# femto.net
KiCad netlist of a schematic drawn in EAGLE
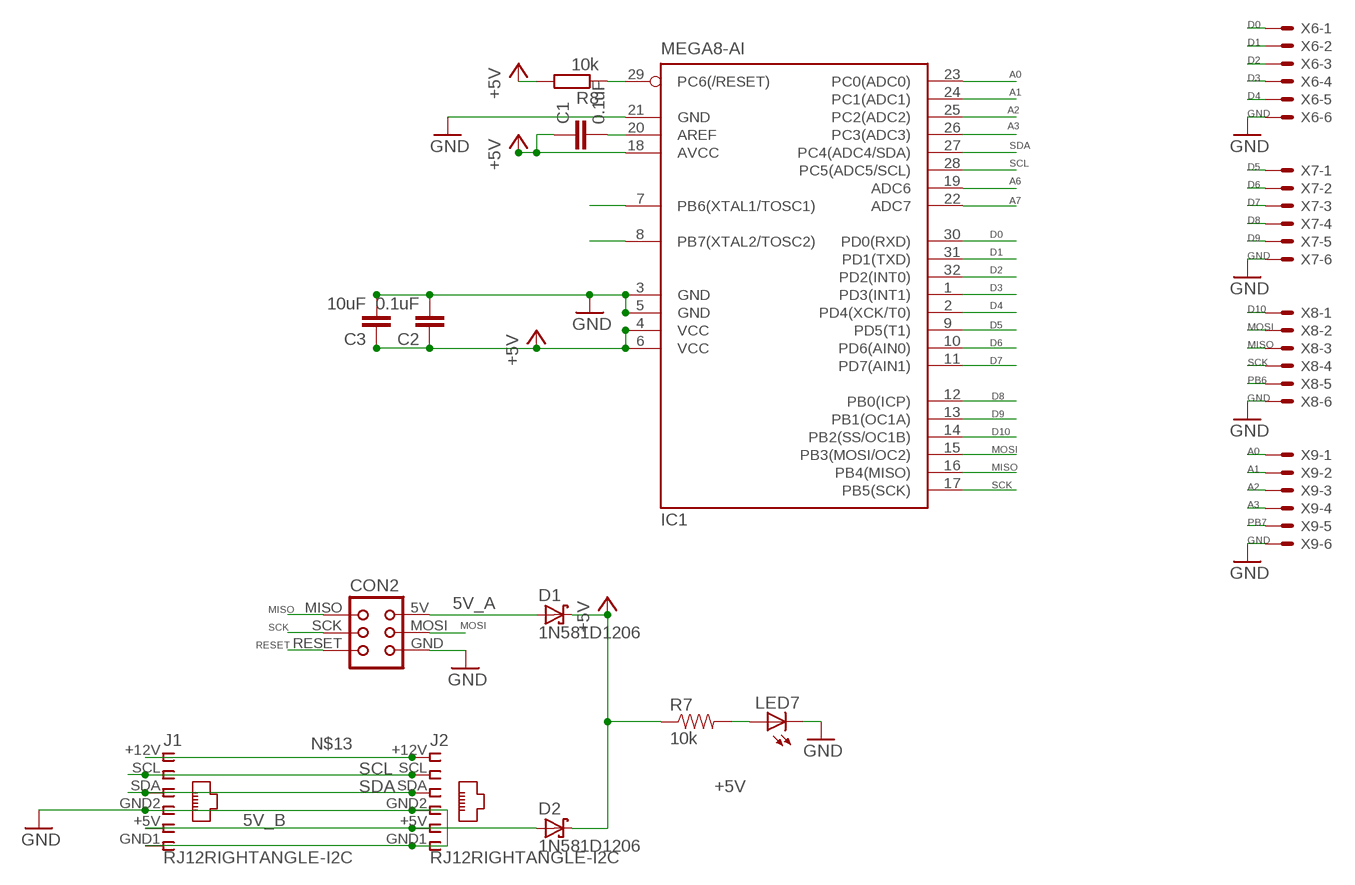
[diagram p0: schematic, sheet 1]

(export (version "E")
  (design (tool "Eeschema 10.0.6"))
  (components
    (comp (ref "C1")
      (value "0.1uF")
      (footprint "eagle-import:C1206")
      (libsource (lib "eagle-import") (part "C-EUC1206"))
    )
    (comp (ref "C2")
      (value "0.1uF")
      (footprint "eagle-import:C1206")
      (libsource (lib "eagle-import") (part "C-EUC1206"))
    )
    (comp (ref "C3")
      (value "10uF")
      (footprint "eagle-import:C1206")
      (libsource (lib "eagle-import") (part "C-EUC1206"))
    )
    (comp (ref "CON2")
      (value "TINYISPTAG")
      (footprint "eagle-import:TC2030-MCP")
      (libsource (lib "eagle-import") (part "TINYISPTAG"))
    )
    (comp (ref "D1")
      (value "1N581D1206")
      (footprint "eagle-import:LED-1206")
      (libsource (lib "eagle-import") (part "1N581D1206"))
    )
    (comp (ref "D2")
      (value "1N581D1206")
      (footprint "eagle-import:LED-1206")
      (libsource (lib "eagle-import") (part "1N581D1206"))
    )
    (comp (ref "IC1")
      (value "MEGA8-AI")
      (footprint "eagle-import:TQFP32-08")
      (fields (field (name "MPN") "ATMEGA8-16AU"))
      (libsource (lib "eagle-import") (part "MEGA8-AI"))
    )
    (comp (ref "J1")
      (value "RJ12RIGHTANGLE-I2C")
      (footprint "eagle-import:RJ12-RIGHTANGLE-I2C")
      (libsource (lib "eagle-import") (part "RJ12RIGHTANGLE-I2C"))
    )
    (comp (ref "J2")
      (value "RJ12RIGHTANGLE-I2C")
      (footprint "eagle-import:RJ12-RIGHTANGLE-I2C")
      (libsource (lib "eagle-import") (part "RJ12RIGHTANGLE-I2C"))
    )
    (comp (ref "LED7")
      (value "LEDCHIP-LED0603")
      (footprint "eagle-import:CHIP-LED0603")
      (libsource (lib "eagle-import") (part "LEDCHIP-LED0603"))
    )
    (comp (ref "R7")
      (value "10k")
      (footprint "eagle-import:0603-RES")
      (libsource (lib "eagle-import") (part "RESISTOR0603-RES"))
    )
    (comp (ref "R8")
      (value "10k")
      (footprint "eagle-import:M1206")
      (libsource (lib "eagle-import") (part "R-EU_M1206"))
    )
    (comp (ref "X6")
      (value "22-23-2061")
      (footprint "eagle-import:22-23-2061")
      (fields (field (name "MF") "MOLEX"))
      (libsource (lib "eagle-import") (part "22-23-2061"))
    )
    (comp (ref "X7")
      (value "22-23-2061")
      (footprint "eagle-import:22-23-2061")
      (fields (field (name "MF") "MOLEX"))
      (libsource (lib "eagle-import") (part "22-23-2061"))
    )
    (comp (ref "X8")
      (value "22-23-2061")
      (footprint "eagle-import:22-23-2061")
      (fields (field (name "MF") "MOLEX"))
      (libsource (lib "eagle-import") (part "22-23-2061"))
    )
    (comp (ref "X9")
      (value "22-23-2061")
      (footprint "eagle-import:22-23-2061")
      (fields (field (name "MF") "MOLEX"))
      (libsource (lib "eagle-import") (part "22-23-2061"))
    )
  )
  (nets
    (net (code "1") (name "+5V") (class "Default")
      (node (ref "C1") (pin "1") (pinfunction "1_1") (pintype "passive"))
      (node (ref "C2") (pin "1") (pinfunction "1_1") (pintype "passive"))
      (node (ref "C3") (pin "1") (pinfunction "1_1") (pintype "passive"))
      (node (ref "D1") (pin "C") (pinfunction "C_C") (pintype "passive"))
      (node (ref "D2") (pin "C") (pinfunction "C_C") (pintype "passive"))
      (node (ref "IC1") (pin "18") (pinfunction "AVCC_18") (pintype "power_in"))
      (node (ref "IC1") (pin "4") (pinfunction "VCC_4") (pintype "power_in"))
      (node (ref "IC1") (pin "6") (pinfunction "VCC_6") (pintype "power_in"))
      (node (ref "R7") (pin "1") (pinfunction "1_1") (pintype "passive"))
      (node (ref "R8") (pin "2") (pinfunction "2_2") (pintype "passive"))
    )
    (net (code "2") (name "/5V_A") (class "Default")
      (node (ref "CON2") (pin "5V") (pinfunction "VCC_5V") (pintype "passive"))
      (node (ref "D1") (pin "A") (pinfunction "A_A") (pintype "passive"))
    )
    (net (code "3") (name "/5V_B") (class "Default")
      (node (ref "D2") (pin "A") (pinfunction "A_A") (pintype "passive"))
      (node (ref "J1") (pin "+5V") (pinfunction "5_+5V") (pintype "bidirectional"))
      (node (ref "J2") (pin "+5V") (pinfunction "5_+5V") (pintype "bidirectional"))
    )
    (net (code "4") (name "/A0") (class "Default")
      (node (ref "IC1") (pin "23") (pinfunction "PC0(ADC0)_23") (pintype "bidirectional"))
      (node (ref "X9") (pin "1") (pinfunction "S_1") (pintype "passive"))
    )
    (net (code "5") (name "/A1") (class "Default")
      (node (ref "IC1") (pin "24") (pinfunction "PC1(ADC1)_24") (pintype "bidirectional"))
      (node (ref "X9") (pin "2") (pinfunction "S_2") (pintype "passive"))
    )
    (net (code "6") (name "/A2") (class "Default")
      (node (ref "IC1") (pin "25") (pinfunction "PC2(ADC2)_25") (pintype "bidirectional"))
      (node (ref "X9") (pin "3") (pinfunction "S_3") (pintype "passive"))
    )
    (net (code "7") (name "/A3") (class "Default")
      (node (ref "IC1") (pin "26") (pinfunction "PC3(ADC3)_26") (pintype "bidirectional"))
      (node (ref "X9") (pin "4") (pinfunction "S_4") (pintype "passive"))
    )
    (net (code "8") (name "/A6") (class "Default")
      (node (ref "IC1") (pin "19") (pinfunction "ADC6_19") (pintype "bidirectional"))
    )
    (net (code "9") (name "/A7") (class "Default")
      (node (ref "IC1") (pin "22") (pinfunction "ADC7_22") (pintype "bidirectional"))
    )
    (net (code "10") (name "/D0") (class "Default")
      (node (ref "IC1") (pin "30") (pinfunction "PD0(RXD)_30") (pintype "bidirectional"))
      (node (ref "X6") (pin "1") (pinfunction "S_1") (pintype "passive"))
    )
    (net (code "11") (name "/D1") (class "Default")
      (node (ref "IC1") (pin "31") (pinfunction "PD1(TXD)_31") (pintype "bidirectional"))
      (node (ref "X6") (pin "2") (pinfunction "S_2") (pintype "passive"))
    )
    (net (code "12") (name "/D2") (class "Default")
      (node (ref "IC1") (pin "32") (pinfunction "PD2(INT0)_32") (pintype "bidirectional"))
      (node (ref "X6") (pin "3") (pinfunction "S_3") (pintype "passive"))
    )
    (net (code "13") (name "/D3") (class "Default")
      (node (ref "IC1") (pin "1") (pinfunction "PD3(INT1)_1") (pintype "bidirectional"))
      (node (ref "X6") (pin "4") (pinfunction "S_4") (pintype "passive"))
    )
    (net (code "14") (name "/D4") (class "Default")
      (node (ref "IC1") (pin "2") (pinfunction "PD4(XCK/T0)_2") (pintype "bidirectional"))
      (node (ref "X6") (pin "5") (pinfunction "S_5") (pintype "passive"))
    )
    (net (code "15") (name "/D5") (class "Default")
      (node (ref "IC1") (pin "9") (pinfunction "PD5(T1)_9") (pintype "bidirectional"))
      (node (ref "X7") (pin "1") (pinfunction "S_1") (pintype "passive"))
    )
    (net (code "16") (name "/D6") (class "Default")
      (node (ref "IC1") (pin "10") (pinfunction "PD6(AIN0)_10") (pintype "bidirectional"))
      (node (ref "X7") (pin "2") (pinfunction "S_2") (pintype "passive"))
    )
    (net (code "17") (name "/D7") (class "Default")
      (node (ref "IC1") (pin "11") (pinfunction "PD7(AIN1)_11") (pintype "bidirectional"))
      (node (ref "X7") (pin "3") (pinfunction "S_3") (pintype "passive"))
    )
    (net (code "18") (name "/D8") (class "Default")
      (node (ref "IC1") (pin "12") (pinfunction "PB0(ICP)_12") (pintype "bidirectional"))
      (node (ref "X7") (pin "4") (pinfunction "S_4") (pintype "passive"))
    )
    (net (code "19") (name "/D9") (class "Default")
      (node (ref "IC1") (pin "13") (pinfunction "PB1(OC1A)_13") (pintype "bidirectional"))
      (node (ref "X7") (pin "5") (pinfunction "S_5") (pintype "passive"))
    )
    (net (code "20") (name "/D10") (class "Default")
      (node (ref "IC1") (pin "14") (pinfunction "PB2(SS/OC1B)_14") (pintype "bidirectional"))
      (node (ref "X8") (pin "1") (pinfunction "S_1") (pintype "passive"))
    )
    (net (code "21") (name "/MISO") (class "Default")
      (node (ref "CON2") (pin "MISO") (pinfunction "MISO_MISO") (pintype "passive"))
      (node (ref "IC1") (pin "16") (pinfunction "PB4(MISO)_16") (pintype "bidirectional"))
      (node (ref "X8") (pin "3") (pinfunction "S_3") (pintype "passive"))
    )
    (net (code "22") (name "/MOSI") (class "Default")
      (node (ref "CON2") (pin "MOSI") (pinfunction "MOSI_MOSI") (pintype "passive"))
      (node (ref "IC1") (pin "15") (pinfunction "PB3(MOSI/OC2)_15") (pintype "bidirectional"))
      (node (ref "X8") (pin "2") (pinfunction "S_2") (pintype "passive"))
    )
    (net (code "23") (name "/N$13") (class "Default")
      (node (ref "J1") (pin "+12V") (pinfunction "1_+12V") (pintype "bidirectional"))
      (node (ref "J2") (pin "+12V") (pinfunction "1_+12V") (pintype "bidirectional"))
    )
    (net (code "24") (name "/PB6") (class "Default")
      (node (ref "IC1") (pin "7") (pinfunction "PB6(XTAL1/TOSC1)_7") (pintype "bidirectional"))
      (node (ref "X8") (pin "5") (pinfunction "S_5") (pintype "passive"))
    )
    (net (code "25") (name "/PB7") (class "Default")
      (node (ref "IC1") (pin "8") (pinfunction "PB7(XTAL2/TOSC2)_8") (pintype "bidirectional"))
      (node (ref "X9") (pin "5") (pinfunction "S_5") (pintype "passive"))
    )
    (net (code "26") (name "/RESET") (class "Default")
      (node (ref "CON2") (pin "RESET") (pinfunction "RESET_RESET") (pintype "passive"))
      (node (ref "IC1") (pin "29") (pinfunction "PC6(/RESET)_29") (pintype "bidirectional"))
      (node (ref "R8") (pin "1") (pinfunction "1_1") (pintype "passive"))
    )
    (net (code "27") (name "/SCK") (class "Default")
      (node (ref "CON2") (pin "SCK") (pinfunction "SCK_SCK") (pintype "passive"))
      (node (ref "IC1") (pin "17") (pinfunction "PB5(SCK)_17") (pintype "bidirectional"))
      (node (ref "X8") (pin "4") (pinfunction "S_4") (pintype "passive"))
    )
    (net (code "28") (name "/SCL") (class "Default")
      (node (ref "IC1") (pin "28") (pinfunction "PC5(ADC5/SCL)_28") (pintype "bidirectional"))
      (node (ref "J1") (pin "SCL") (pinfunction "2_SCL") (pintype "bidirectional"))
      (node (ref "J2") (pin "SCL") (pinfunction "2_SCL") (pintype "bidirectional"))
    )
    (net (code "29") (name "/SDA") (class "Default")
      (node (ref "IC1") (pin "27") (pinfunction "PC4(ADC4/SDA)_27") (pintype "bidirectional"))
      (node (ref "J1") (pin "SDA") (pinfunction "3_SDA") (pintype "bidirectional"))
      (node (ref "J2") (pin "SDA") (pinfunction "3_SDA") (pintype "bidirectional"))
    )
    (net (code "30") (name "GND") (class "Default")
      (node (ref "C2") (pin "2") (pinfunction "2_2") (pintype "passive"))
      (node (ref "C3") (pin "2") (pinfunction "2_2") (pintype "passive"))
      (node (ref "CON2") (pin "GND") (pinfunction "GND_GND") (pintype "passive"))
      (node (ref "IC1") (pin "21") (pinfunction "GND_21") (pintype "power_in"))
      (node (ref "IC1") (pin "3") (pinfunction "GND_3") (pintype "power_in"))
      (node (ref "IC1") (pin "5") (pinfunction "GND_5") (pintype "power_in"))
      (node (ref "J1") (pin "GND1") (pinfunction "6_GND1") (pintype "bidirectional"))
      (node (ref "J1") (pin "GND2") (pinfunction "4_GND2") (pintype "bidirectional"))
      (node (ref "J2") (pin "GND1") (pinfunction "6_GND1") (pintype "bidirectional"))
      (node (ref "J2") (pin "GND2") (pinfunction "4_GND2") (pintype "bidirectional"))
      (node (ref "LED7") (pin "C") (pinfunction "C_C") (pintype "passive"))
      (node (ref "X6") (pin "6") (pinfunction "S_6") (pintype "passive"))
      (node (ref "X7") (pin "6") (pinfunction "S_6") (pintype "passive"))
      (node (ref "X8") (pin "6") (pinfunction "S_6") (pintype "passive"))
      (node (ref "X9") (pin "6") (pinfunction "S_6") (pintype "passive"))
    )
    (net (code "31") (name "Net-(IC1-AREF)") (class "Default")
      (node (ref "C1") (pin "2") (pinfunction "2_2") (pintype "passive"))
      (node (ref "IC1") (pin "20") (pinfunction "AREF_20") (pintype "passive"))
    )
    (net (code "32") (name "Net-(LED7-PadA)") (class "Default")
      (node (ref "LED7") (pin "A") (pinfunction "A_A") (pintype "passive"))
      (node (ref "R7") (pin "2") (pinfunction "2_2") (pintype "passive"))
    )
  )
)
